# blackfin_e_lcd_keypad.net
KiCad netlist of a schematic drawn in Altium Designer
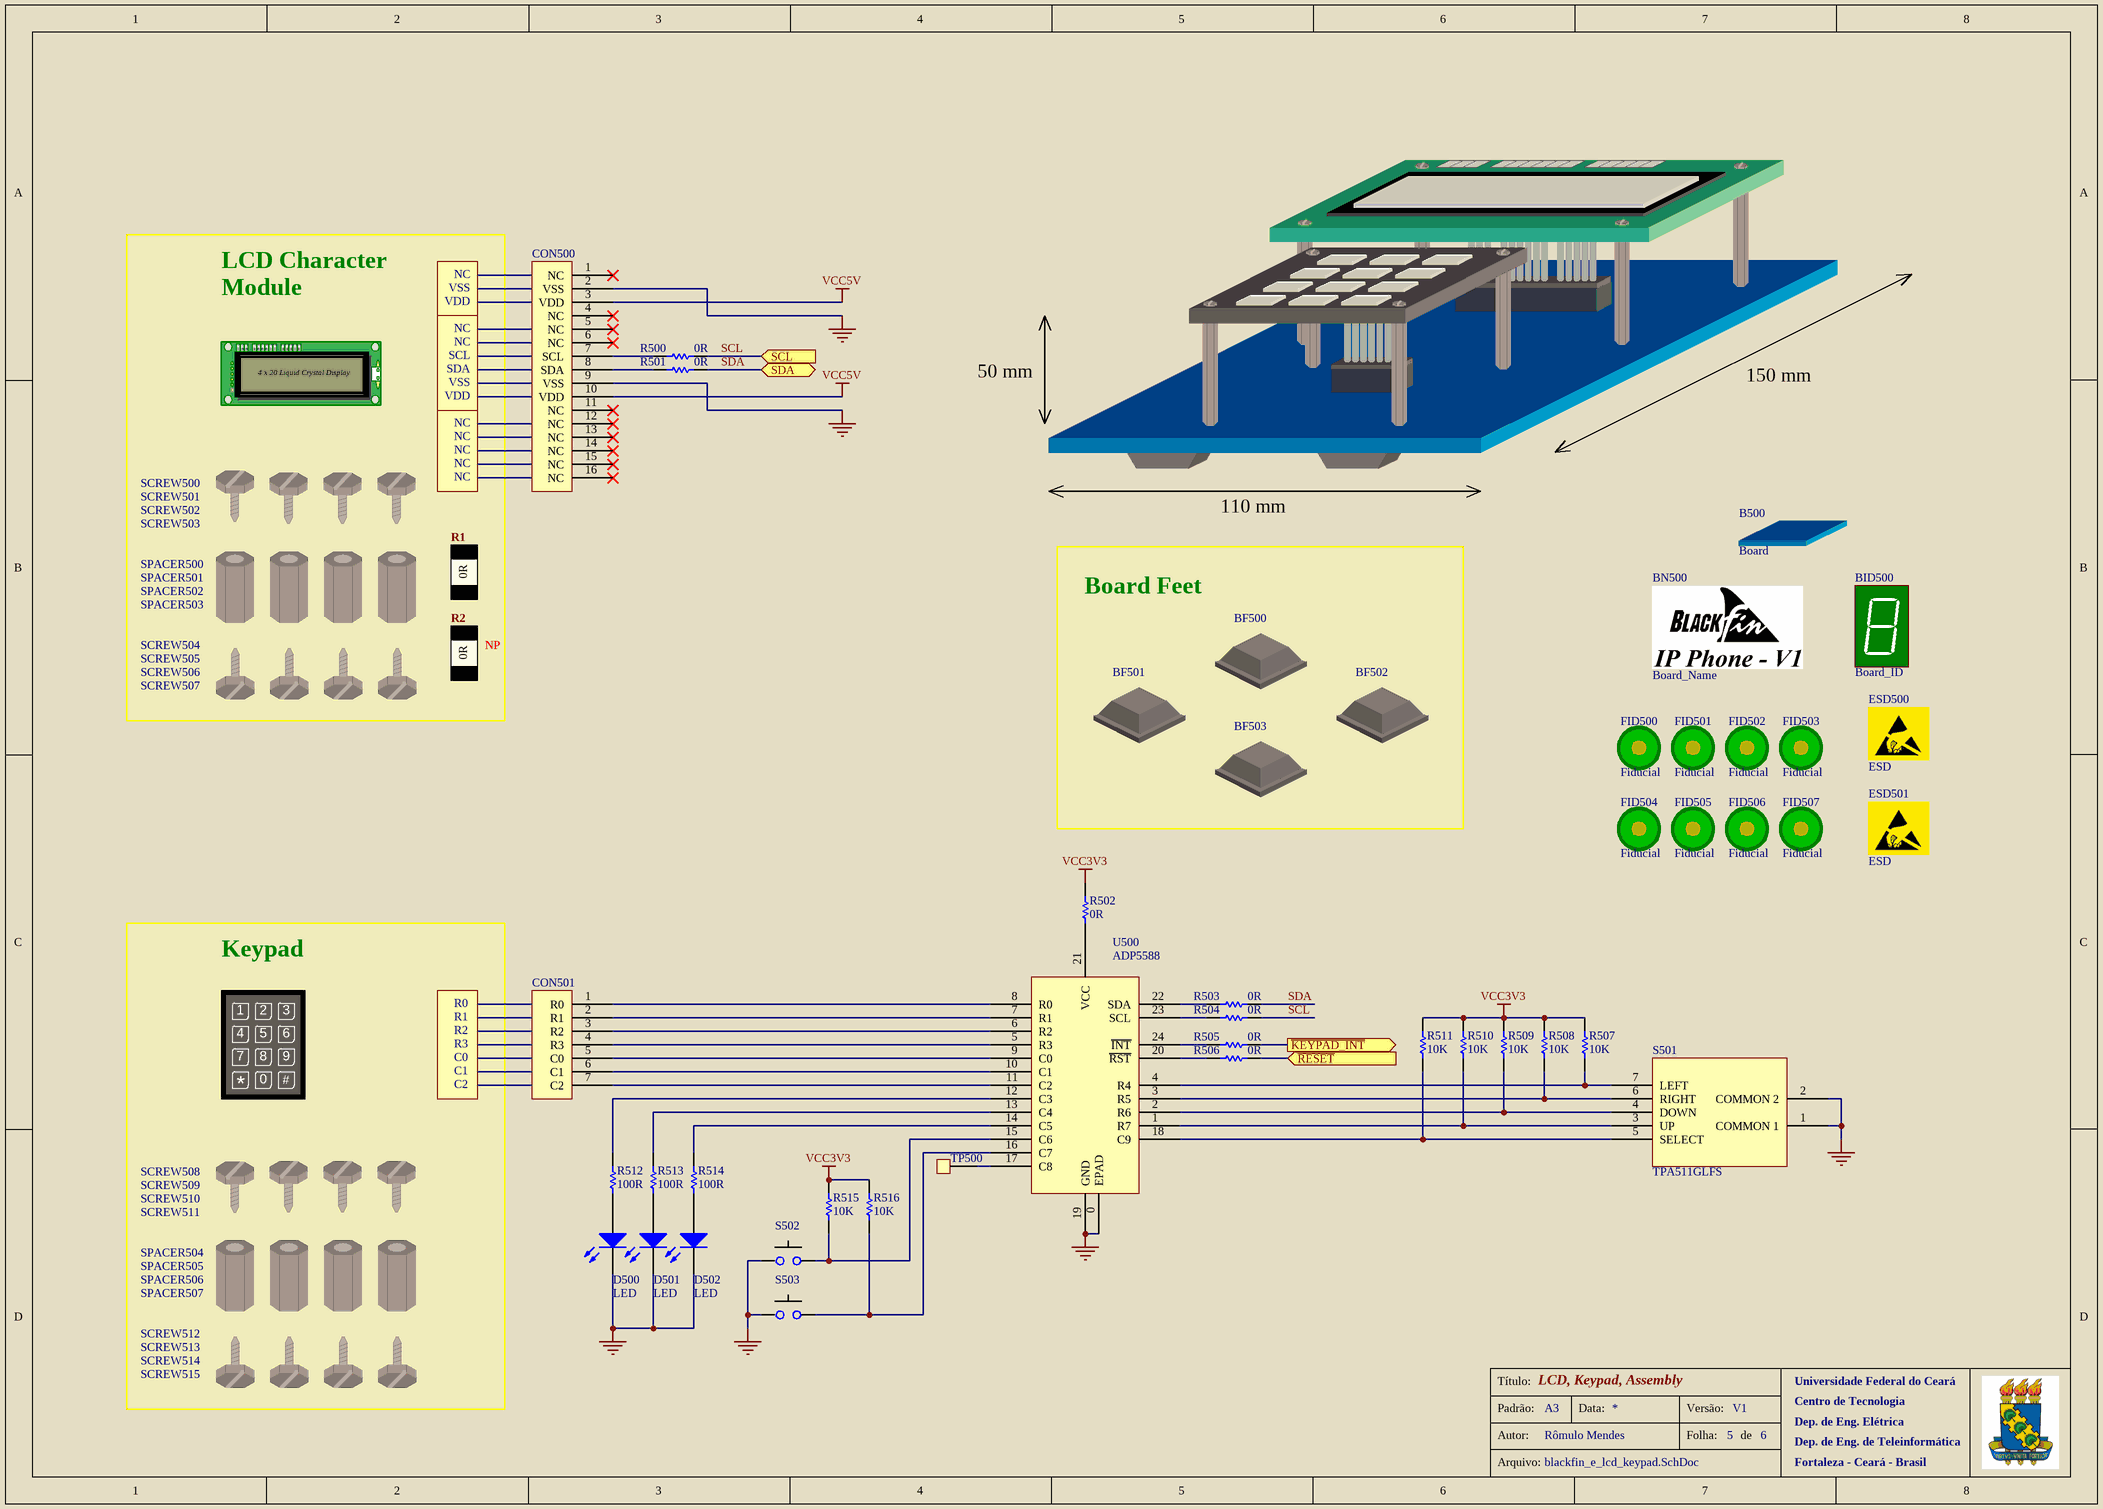
[diagram p0: blackfin_e_lcd_keypad.SchDoc]

(export (version "E")
  (design (tool "Eeschema 10.0.6"))
  (components
    (comp (ref "B500")
      (value "Board")
      (fields (field (name "EVENDORPART#") "NÃO SE APLICA"))
      (libsource (lib "blackfin_schlib") (part "Board"))
    )
    (comp (ref "BF500")
      (value "Board Foot")
      (footprint "blackfin_pcblib:Board Foot (Hemisphere)")
      (fields
        (field (name "EVENDORPART#") "517-SJ-5003BK")
        (field (name "PART#") "SJ-5003 (BLACK)")
        (field (name "MANUFACTURER") "3M Electronic Specialty")
      )
      (libsource (lib "*") (part "Board Foot"))
    )
    (comp (ref "BF501")
      (value "Board Foot")
      (footprint "blackfin_pcblib:Board Foot (Hemisphere)")
      (fields
        (field (name "EVENDORPART#") "517-SJ-5003BK")
        (field (name "PART#") "SJ-5003 (BLACK)")
        (field (name "MANUFACTURER") "3M Electronic Specialty")
      )
      (libsource (lib "*") (part "Board Foot"))
    )
    (comp (ref "BF502")
      (value "Board Foot")
      (footprint "blackfin_pcblib:Board Foot (Hemisphere)")
      (fields
        (field (name "EVENDORPART#") "517-SJ-5003BK")
        (field (name "PART#") "SJ-5003 (BLACK)")
        (field (name "MANUFACTURER") "3M Electronic Specialty")
      )
      (libsource (lib "*") (part "Board Foot"))
    )
    (comp (ref "BF503")
      (value "Board Foot")
      (footprint "blackfin_pcblib:Board Foot (Hemisphere)")
      (fields
        (field (name "EVENDORPART#") "517-SJ-5003BK")
        (field (name "PART#") "SJ-5003 (BLACK)")
        (field (name "MANUFACTURER") "3M Electronic Specialty")
      )
      (libsource (lib "*") (part "Board Foot"))
    )
    (comp (ref "BID500")
      (value "Board_ID")
      (footprint "blackfin_pcblib:BOARD_ID")
      (fields (field (name "EVENDORPART#") "NÃO SE APLICA"))
      (libsource (lib "blackfin_schlib") (part "Board_ID"))
    )
    (comp (ref "BN500")
      (value "Board_Name")
      (footprint "blackfin_pcblib:LOGO")
      (fields (field (name "EVENDORPART#") "NÃO SE APLICA"))
      (libsource (lib "blackfin_schlib") (part "Board_Name"))
    )
    (comp (ref "CON500")
      (value "LCD_Connector")
      (footprint "blackfin_pcblib:SOCKET_1x16")
      (fields (field (name "EVENDORPART#") "SSM-116-L-SV") (field (name "MANUFACTURER") "Samtec"))
      (libsource (lib "blackfin_schlib") (part "LCD_Connector"))
    )
    (comp (ref "CON501")
      (value "Keypad_Connector")
      (footprint "blackfin_pcblib:SOCKET_1x7")
      (fields (field (name "EVENDORPART#") "SSM-107-L-SV") (field (name "MANUFACTURER") "Samtec"))
      (libsource (lib "blackfin_schlib") (part "Keypad_Connector"))
    )
    (comp (ref "D500")
      (value "LED")
      (footprint "blackfin_pcblib:LED_0603")
      (description "Red LED")
      (fields (field (name "EVENDORPART#") "638-QTLP600C2TR") (field (name "MANUFACTURER") "Everlight"))
      (libsource (lib "blackfin_schlib") (part "LED"))
    )
    (comp (ref "D501")
      (value "LED")
      (footprint "blackfin_pcblib:LED_0603")
      (description "Red LED")
      (fields (field (name "EVENDORPART#") "638-QTLP600C2TR") (field (name "MANUFACTURER") "Everlight"))
      (libsource (lib "blackfin_schlib") (part "LED"))
    )
    (comp (ref "D502")
      (value "LED")
      (footprint "blackfin_pcblib:LED_0603")
      (description "Red LED")
      (fields (field (name "EVENDORPART#") "638-QTLP600C2TR") (field (name "MANUFACTURER") "Everlight"))
      (libsource (lib "blackfin_schlib") (part "LED"))
    )
    (comp (ref "ESD500")
      (value "ESD")
      (footprint "blackfin_pcblib:ESD")
      (fields (field (name "EVENDORPART#") "NÃO SE APLICA"))
      (libsource (lib "blackfin_schlib") (part "ESD"))
    )
    (comp (ref "ESD501")
      (value "ESD")
      (footprint "blackfin_pcblib:ESD")
      (fields (field (name "EVENDORPART#") "NÃO SE APLICA"))
      (libsource (lib "blackfin_schlib") (part "ESD"))
    )
    (comp (ref "FID500")
      (value "Fiducial")
      (footprint "blackfin_pcblib:Fiducial")
      (fields (field (name "EVENDORPART#") "NÃO SE APLICA"))
      (libsource (lib "blackfin_schlib") (part "Fiducial"))
    )
    (comp (ref "FID501")
      (value "Fiducial")
      (footprint "blackfin_pcblib:Fiducial")
      (fields (field (name "EVENDORPART#") "NÃO SE APLICA"))
      (libsource (lib "blackfin_schlib") (part "Fiducial"))
    )
    (comp (ref "FID502")
      (value "Fiducial")
      (footprint "blackfin_pcblib:Fiducial")
      (fields (field (name "EVENDORPART#") "NÃO SE APLICA"))
      (libsource (lib "blackfin_schlib") (part "Fiducial"))
    )
    (comp (ref "FID503")
      (value "Fiducial")
      (footprint "blackfin_pcblib:Fiducial")
      (fields (field (name "EVENDORPART#") "NÃO SE APLICA"))
      (libsource (lib "blackfin_schlib") (part "Fiducial"))
    )
    (comp (ref "FID504")
      (value "Fiducial")
      (footprint "blackfin_pcblib:Fiducial")
      (fields (field (name "EVENDORPART#") "NÃO SE APLICA"))
      (libsource (lib "blackfin_schlib") (part "Fiducial"))
    )
    (comp (ref "FID505")
      (value "Fiducial")
      (footprint "blackfin_pcblib:Fiducial")
      (fields (field (name "EVENDORPART#") "NÃO SE APLICA"))
      (libsource (lib "blackfin_schlib") (part "Fiducial"))
    )
    (comp (ref "FID506")
      (value "Fiducial")
      (footprint "blackfin_pcblib:Fiducial")
      (fields (field (name "EVENDORPART#") "NÃO SE APLICA"))
      (libsource (lib "blackfin_schlib") (part "Fiducial"))
    )
    (comp (ref "FID507")
      (value "Fiducial")
      (footprint "blackfin_pcblib:Fiducial")
      (fields (field (name "EVENDORPART#") "NÃO SE APLICA"))
      (libsource (lib "blackfin_schlib") (part "Fiducial"))
    )
    (comp (ref "KEYPAD_HEADER500")
      (value "Keypad_Header_1x7")
      (fields (field (name "EVENDORPART#") "ESQ-107-34-L-S") (field (name "MANUFACTURER") "Samtec"))
      (libsource (lib "blackfin_schlib") (part "Keypad_Header_1x7"))
    )
    (comp (ref "LCD500")
      (value "LCD")
      (footprint "blackfin_pcblib:LCD")
      (fields
        (field (name "EVENDORPART#") "763-0420D3Z-FL-GBW")
        (field (name "PART#") "NHD-0420D3Z-FL-GBW")
        (field (name "MANUFACTURER") "Newhaven")
      )
      (libsource (lib "*") (part "LCD"))
    )
    (comp (ref "LCD_HEADER500")
      (value "LCD_Header_1x3")
      (fields (field (name "EVENDORPART#") "DW-03-12-F-S-694") (field (name "MANUFACTURER") "Samtec"))
      (libsource (lib "blackfin_schlib") (part "LCD_Header_1x3"))
    )
    (comp (ref "LCD_HEADER501")
      (value "LCD_Header_1x6")
      (fields (field (name "EVENDORPART#") "DW-06-12-F-S-694") (field (name "MANUFACTURER") "Samtec"))
      (libsource (lib "blackfin_schlib") (part "LCD_Header_1x6"))
    )
    (comp (ref "LCD_HEADER502")
      (value "LCD_Header_1x5")
      (fields (field (name "EVENDORPART#") "DW-05-12-F-S-694") (field (name "MANUFACTURER") "Samtec"))
      (libsource (lib "blackfin_schlib") (part "LCD_Header_1x5"))
    )
    (comp (ref "LCD_RES500")
      (value "LCD_Resistor")
      (fields
        (field (name "EVENDORPART#") "71-CRCW0805-0-E3")
        (field (name "MANUFACTURER") "Vishay/Dale")
        (field (name "PART#") "CRCW08050000Z0EA")
      )
      (libsource (lib "blackfin_schlib") (part "LCD_Resistor"))
    )
    (comp (ref "LCD_RES501")
      (value "LCD_Resistor")
      (fields
        (field (name "EVENDORPART#") "71-CRCW0805-0-E3")
        (field (name "MANUFACTURER") "Vishay/Dale")
        (field (name "PART#") "CRCW08050000Z0EA")
      )
      (libsource (lib "blackfin_schlib") (part "LCD_Resistor"))
    )
    (comp (ref "R500")
      (value "0R")
      (footprint "blackfin_pcblib:R_0603")
      (fields
        (field (name "EVENDORPART#") "71-CRCW06030000Z0EB")
        (field (name "PART#") "CRCW06030000Z0EB")
        (field (name "MANUFACTURER") "Vishay/Dale")
      )
      (libsource (lib "blackfin_schlib") (part "Resistor"))
    )
    (comp (ref "R501")
      (value "0R")
      (footprint "blackfin_pcblib:R_0603")
      (fields
        (field (name "EVENDORPART#") "71-CRCW06030000Z0EB")
        (field (name "PART#") "CRCW06030000Z0EB")
        (field (name "MANUFACTURER") "Vishay/Dale")
      )
      (libsource (lib "blackfin_schlib") (part "Resistor"))
    )
    (comp (ref "R502")
      (value "0R")
      (footprint "blackfin_pcblib:R_0603")
      (fields
        (field (name "EVENDORPART#") "71-CRCW06030000Z0EB")
        (field (name "PART#") "CRCW06030000Z0EB")
        (field (name "MANUFACTURER") "Vishay/Dale")
      )
      (libsource (lib "blackfin_schlib") (part "Resistor"))
    )
    (comp (ref "R503")
      (value "0R")
      (footprint "blackfin_pcblib:R_0603")
      (fields
        (field (name "EVENDORPART#") "71-CRCW06030000Z0EB")
        (field (name "PART#") "CRCW06030000Z0EB")
        (field (name "MANUFACTURER") "Vishay/Dale")
      )
      (libsource (lib "blackfin_schlib") (part "Resistor"))
    )
    (comp (ref "R504")
      (value "0R")
      (footprint "blackfin_pcblib:R_0603")
      (fields
        (field (name "EVENDORPART#") "71-CRCW06030000Z0EB")
        (field (name "PART#") "CRCW06030000Z0EB")
        (field (name "MANUFACTURER") "Vishay/Dale")
      )
      (libsource (lib "blackfin_schlib") (part "Resistor"))
    )
    (comp (ref "R505")
      (value "0R")
      (footprint "blackfin_pcblib:R_0603")
      (fields
        (field (name "EVENDORPART#") "71-CRCW06030000Z0EB")
        (field (name "PART#") "CRCW06030000Z0EB")
        (field (name "MANUFACTURER") "Vishay/Dale")
      )
      (libsource (lib "blackfin_schlib") (part "Resistor"))
    )
    (comp (ref "R506")
      (value "0R")
      (footprint "blackfin_pcblib:R_0603")
      (fields
        (field (name "EVENDORPART#") "71-CRCW06030000Z0EB")
        (field (name "PART#") "CRCW06030000Z0EB")
        (field (name "MANUFACTURER") "Vishay/Dale")
      )
      (libsource (lib "blackfin_schlib") (part "Resistor"))
    )
    (comp (ref "R507")
      (value "10K")
      (footprint "blackfin_pcblib:R_0603")
      (fields
        (field (name "EVENDORPART#") "71-CRCW0603-10K-E3")
        (field (name "PART#") "CRCW060310K0FKEA")
        (field (name "MANUFACTURER") "Vishay/Dale")
      )
      (libsource (lib "blackfin_schlib") (part "Resistor"))
    )
    (comp (ref "R508")
      (value "10K")
      (footprint "blackfin_pcblib:R_0603")
      (fields
        (field (name "EVENDORPART#") "71-CRCW0603-10K-E3")
        (field (name "PART#") "CRCW060310K0FKEA")
        (field (name "MANUFACTURER") "Vishay/Dale")
      )
      (libsource (lib "blackfin_schlib") (part "Resistor"))
    )
    (comp (ref "R509")
      (value "10K")
      (footprint "blackfin_pcblib:R_0603")
      (fields
        (field (name "EVENDORPART#") "71-CRCW0603-10K-E3")
        (field (name "PART#") "CRCW060310K0FKEA")
        (field (name "MANUFACTURER") "Vishay/Dale")
      )
      (libsource (lib "blackfin_schlib") (part "Resistor"))
    )
    (comp (ref "R510")
      (value "10K")
      (footprint "blackfin_pcblib:R_0603")
      (fields
        (field (name "EVENDORPART#") "71-CRCW0603-10K-E3")
        (field (name "PART#") "CRCW060310K0FKEA")
        (field (name "MANUFACTURER") "Vishay/Dale")
      )
      (libsource (lib "blackfin_schlib") (part "Resistor"))
    )
    (comp (ref "R511")
      (value "10K")
      (footprint "blackfin_pcblib:R_0603")
      (fields
        (field (name "EVENDORPART#") "71-CRCW0603-10K-E3")
        (field (name "PART#") "CRCW060310K0FKEA")
        (field (name "MANUFACTURER") "Vishay/Dale")
      )
      (libsource (lib "blackfin_schlib") (part "Resistor"))
    )
    (comp (ref "R512")
      (value "100R")
      (footprint "blackfin_pcblib:R_0603")
      (fields
        (field (name "EVENDORPART#") "71-CRCW0603-100-E3")
        (field (name "PART#") "CRCW0603100RFKEA")
        (field (name "MANUFACTURER") "Vishay/Dale")
      )
      (libsource (lib "blackfin_schlib") (part "Resistor"))
    )
    (comp (ref "R513")
      (value "100R")
      (footprint "blackfin_pcblib:R_0603")
      (fields
        (field (name "EVENDORPART#") "71-CRCW0603-100-E3")
        (field (name "PART#") "CRCW0603100RFKEA")
        (field (name "MANUFACTURER") "Vishay/Dale")
      )
      (libsource (lib "blackfin_schlib") (part "Resistor"))
    )
    (comp (ref "R514")
      (value "100R")
      (footprint "blackfin_pcblib:R_0603")
      (fields
        (field (name "EVENDORPART#") "71-CRCW0603-100-E3")
        (field (name "PART#") "CRCW0603100RFKEA")
        (field (name "MANUFACTURER") "Vishay/Dale")
      )
      (libsource (lib "blackfin_schlib") (part "Resistor"))
    )
    (comp (ref "R515")
      (value "10K")
      (footprint "blackfin_pcblib:R_0603")
      (fields
        (field (name "EVENDORPART#") "71-CRCW0603-10K-E3")
        (field (name "PART#") "CRCW060310K0FKEA")
        (field (name "MANUFACTURER") "Vishay/Dale")
      )
      (libsource (lib "blackfin_schlib") (part "Resistor"))
    )
    (comp (ref "R516")
      (value "10K")
      (footprint "blackfin_pcblib:R_0603")
      (fields
        (field (name "EVENDORPART#") "71-CRCW0603-10K-E3")
        (field (name "PART#") "CRCW060310K0FKEA")
        (field (name "MANUFACTURER") "Vishay/Dale")
      )
      (libsource (lib "blackfin_schlib") (part "Resistor"))
    )
    (comp (ref "S500")
      (value "Keypad")
      (footprint "blackfin_pcblib:Keypad")
      (fields
        (field (name "EVENDORPART#") "GH5009-ND")
        (field (name "PART#") "96AB2-152-R")
        (field (name "MANUFACTURER") "Grayhill Inc")
      )
      (libsource (lib "blackfin_schlib") (part "Keypad"))
    )
    (comp (ref "S501")
      (value "TPA511GLFS")
      (footprint "blackfin_pcblib:TPA511GLFS")
      (fields (field (name "EVENDORPART#") "611-TPA511GLFS") (field (name "MANUFACTURER") "C&K Components"))
      (libsource (lib "blackfin_schlib") (part "TPA511GLFS"))
    )
    (comp (ref "S502")
      (value "Push Button")
      (footprint "blackfin_pcblib:Push Button")
      (fields
        (field (name "EVENDORPART#") "611-PTS645SH50SMTRLF")
        (field (name "PART#") "PTS645SH50SMTRLFS")
        (field (name "MANUFACTURER") "C&K Components")
      )
      (libsource (lib "*") (part "Push Button"))
    )
    (comp (ref "S503")
      (value "Push Button")
      (footprint "blackfin_pcblib:Push Button")
      (fields
        (field (name "EVENDORPART#") "611-PTS645SH50SMTRLF")
        (field (name "PART#") "PTS645SH50SMTRLFS")
        (field (name "MANUFACTURER") "C&K Components")
      )
      (libsource (lib "*") (part "Push Button"))
    )
    (comp (ref "SCREW500")
      (value "Screw")
      (fields
        (field (name "EVENDORPART#") "534-29301")
        (field (name "PART#") "29301")
        (field (name "MANUFACTURER") "Keystone Electronics")
      )
      (libsource (lib "*") (part "Screw"))
    )
    (comp (ref "SCREW501")
      (value "Screw")
      (fields
        (field (name "EVENDORPART#") "534-29301")
        (field (name "PART#") "29301")
        (field (name "MANUFACTURER") "Keystone Electronics")
      )
      (libsource (lib "*") (part "Screw"))
    )
    (comp (ref "SCREW502")
      (value "Screw")
      (fields
        (field (name "EVENDORPART#") "534-29301")
        (field (name "PART#") "29301")
        (field (name "MANUFACTURER") "Keystone Electronics")
      )
      (libsource (lib "*") (part "Screw"))
    )
    (comp (ref "SCREW503")
      (value "Screw")
      (fields
        (field (name "EVENDORPART#") "534-29301")
        (field (name "PART#") "29301")
        (field (name "MANUFACTURER") "Keystone Electronics")
      )
      (libsource (lib "*") (part "Screw"))
    )
    (comp (ref "SCREW504")
      (value "Screw")
      (fields
        (field (name "EVENDORPART#") "534-29301")
        (field (name "PART#") "29301")
        (field (name "MANUFACTURER") "Keystone Electronics")
      )
      (libsource (lib "*") (part "Screw"))
    )
    (comp (ref "SCREW505")
      (value "Screw")
      (fields
        (field (name "EVENDORPART#") "534-29301")
        (field (name "PART#") "29301")
        (field (name "MANUFACTURER") "Keystone Electronics")
      )
      (libsource (lib "*") (part "Screw"))
    )
    (comp (ref "SCREW506")
      (value "Screw")
      (fields
        (field (name "EVENDORPART#") "534-29301")
        (field (name "PART#") "29301")
        (field (name "MANUFACTURER") "Keystone Electronics")
      )
      (libsource (lib "*") (part "Screw"))
    )
    (comp (ref "SCREW507")
      (value "Screw")
      (fields
        (field (name "EVENDORPART#") "534-29301")
        (field (name "PART#") "29301")
        (field (name "MANUFACTURER") "Keystone Electronics")
      )
      (libsource (lib "*") (part "Screw"))
    )
    (comp (ref "SCREW508")
      (value "Screw")
      (fields
        (field (name "EVENDORPART#") "534-29301")
        (field (name "PART#") "29301")
        (field (name "MANUFACTURER") "Keystone Electronics")
      )
      (libsource (lib "*") (part "Screw"))
    )
    (comp (ref "SCREW509")
      (value "Screw")
      (fields
        (field (name "EVENDORPART#") "534-29301")
        (field (name "PART#") "29301")
        (field (name "MANUFACTURER") "Keystone Electronics")
      )
      (libsource (lib "*") (part "Screw"))
    )
    (comp (ref "SCREW510")
      (value "Screw")
      (fields
        (field (name "EVENDORPART#") "534-29301")
        (field (name "PART#") "29301")
        (field (name "MANUFACTURER") "Keystone Electronics")
      )
      (libsource (lib "*") (part "Screw"))
    )
    (comp (ref "SCREW511")
      (value "Screw")
      (fields
        (field (name "EVENDORPART#") "534-29301")
        (field (name "PART#") "29301")
        (field (name "MANUFACTURER") "Keystone Electronics")
      )
      (libsource (lib "*") (part "Screw"))
    )
    (comp (ref "SCREW512")
      (value "Screw")
      (fields
        (field (name "EVENDORPART#") "534-29301")
        (field (name "PART#") "29301")
        (field (name "MANUFACTURER") "Keystone Electronics")
      )
      (libsource (lib "*") (part "Screw"))
    )
    (comp (ref "SCREW513")
      (value "Screw")
      (fields
        (field (name "EVENDORPART#") "534-29301")
        (field (name "PART#") "29301")
        (field (name "MANUFACTURER") "Keystone Electronics")
      )
      (libsource (lib "*") (part "Screw"))
    )
    (comp (ref "SCREW514")
      (value "Screw")
      (fields
        (field (name "EVENDORPART#") "534-29301")
        (field (name "PART#") "29301")
        (field (name "MANUFACTURER") "Keystone Electronics")
      )
      (libsource (lib "*") (part "Screw"))
    )
    (comp (ref "SCREW515")
      (value "Screw")
      (fields
        (field (name "EVENDORPART#") "534-29301")
        (field (name "PART#") "29301")
        (field (name "MANUFACTURER") "Keystone Electronics")
      )
      (libsource (lib "*") (part "Screw"))
    )
    (comp (ref "SPACER500")
      (value "Spacer")
      (fields
        (field (name "EVENDORPART#") "534-24428")
        (field (name "MANUFACTURER") "Keystone Electronics")
        (field (name "PART#") "24428")
      )
      (libsource (lib "blackfin_schlib") (part "Spacer"))
    )
    (comp (ref "SPACER501")
      (value "Spacer")
      (fields
        (field (name "EVENDORPART#") "534-24428")
        (field (name "MANUFACTURER") "Keystone Electronics")
        (field (name "PART#") "24428")
      )
      (libsource (lib "blackfin_schlib") (part "Spacer"))
    )
    (comp (ref "SPACER502")
      (value "Spacer")
      (fields
        (field (name "EVENDORPART#") "534-24428")
        (field (name "MANUFACTURER") "Keystone Electronics")
        (field (name "PART#") "24428")
      )
      (libsource (lib "blackfin_schlib") (part "Spacer"))
    )
    (comp (ref "SPACER503")
      (value "Spacer")
      (fields
        (field (name "EVENDORPART#") "534-24428")
        (field (name "MANUFACTURER") "Keystone Electronics")
        (field (name "PART#") "24428")
      )
      (libsource (lib "blackfin_schlib") (part "Spacer"))
    )
    (comp (ref "SPACER504")
      (value "Spacer")
      (fields
        (field (name "EVENDORPART#") "534-24428")
        (field (name "MANUFACTURER") "Keystone Electronics")
        (field (name "PART#") "24428")
      )
      (libsource (lib "blackfin_schlib") (part "Spacer"))
    )
    (comp (ref "SPACER505")
      (value "Spacer")
      (fields
        (field (name "EVENDORPART#") "534-24428")
        (field (name "MANUFACTURER") "Keystone Electronics")
        (field (name "PART#") "24428")
      )
      (libsource (lib "blackfin_schlib") (part "Spacer"))
    )
    (comp (ref "SPACER506")
      (value "Spacer")
      (fields
        (field (name "EVENDORPART#") "534-24428")
        (field (name "MANUFACTURER") "Keystone Electronics")
        (field (name "PART#") "24428")
      )
      (libsource (lib "blackfin_schlib") (part "Spacer"))
    )
    (comp (ref "SPACER507")
      (value "Spacer")
      (fields
        (field (name "EVENDORPART#") "534-24428")
        (field (name "MANUFACTURER") "Keystone Electronics")
        (field (name "PART#") "24428")
      )
      (libsource (lib "blackfin_schlib") (part "Spacer"))
    )
    (comp (ref "TP500")
      (value "Test Point")
      (footprint "blackfin_pcblib:Test Point")
      (fields (field (name "EVENDORPART#") "NÃO SE APLICA"))
      (libsource (lib "blackfin_schlib") (part "Test Point"))
    )
    (comp (ref "U500")
      (value "ADP5588")
      (footprint "blackfin_pcblib:QFN-24")
      (fields
        (field (name "EVENDORPART#") "ADP5588ACPZ-R7CT-ND")
        (field (name "PART#") "ADP5588ACPZ-R7")
        (field (name "MANUFACTURER") "Analog Devices")
      )
      (libsource (lib "blackfin_schlib") (part "ADP5588"))
    )
  )
  (nets
    (net (code "1") (name "/SCL") (class "Default")
      (node (ref "R500") (pin "2") (pinfunction "2_2") (pintype "passive"))
      (node (ref "R504") (pin "2") (pinfunction "2_2") (pintype "passive"))
    )
    (net (code "2") (name "/SDA") (class "Default")
      (node (ref "R501") (pin "2") (pinfunction "2_2") (pintype "passive"))
      (node (ref "R503") (pin "2") (pinfunction "2_2") (pintype "passive"))
    )
    (net (code "3") (name "/~{KEYPAD_INT}") (class "Default")
      (node (ref "R505") (pin "2") (pinfunction "2_2") (pintype "passive"))
    )
    (net (code "4") (name "/~{RESET}") (class "Default")
      (node (ref "R506") (pin "2") (pinfunction "2_2") (pintype "passive"))
    )
    (net (code "5") (name "GND") (class "Default")
      (node (ref "CON500") (pin "2") (pinfunction "VSS_2") (pintype "passive"))
      (node (ref "CON500") (pin "9") (pinfunction "VSS_9") (pintype "passive"))
      (node (ref "D500") (pin "2") (pinfunction "K_2") (pintype "passive"))
      (node (ref "D501") (pin "2") (pinfunction "K_2") (pintype "passive"))
      (node (ref "D502") (pin "2") (pinfunction "K_2") (pintype "passive"))
      (node (ref "S501") (pin "1") (pinfunction "COMMON_1_1") (pintype "passive"))
      (node (ref "S501") (pin "2") (pinfunction "COMMON_2_2") (pintype "passive"))
      (node (ref "S502") (pin "1") (pinfunction "1_1") (pintype "passive"))
      (node (ref "S503") (pin "1") (pinfunction "1_1") (pintype "passive"))
      (node (ref "U500") (pin "0") (pinfunction "EPAD_0") (pintype "passive"))
      (node (ref "U500") (pin "19") (pinfunction "GND_19") (pintype "passive"))
    )
    (net (code "6") (name "Net-(CON500-SCL)") (class "Default")
      (node (ref "CON500") (pin "7") (pinfunction "SCL_7") (pintype "passive"))
      (node (ref "R500") (pin "1") (pinfunction "1_1") (pintype "passive"))
    )
    (net (code "7") (name "Net-(CON500-SDA)") (class "Default")
      (node (ref "CON500") (pin "8") (pinfunction "SDA_8") (pintype "passive"))
      (node (ref "R501") (pin "1") (pinfunction "1_1") (pintype "passive"))
    )
    (net (code "8") (name "Net-(CON501-C0)") (class "Default")
      (node (ref "CON501") (pin "5") (pinfunction "C0_5") (pintype "passive"))
      (node (ref "U500") (pin "9") (pinfunction "C0_9") (pintype "passive"))
    )
    (net (code "9") (name "Net-(CON501-C1)") (class "Default")
      (node (ref "CON501") (pin "6") (pinfunction "C1_6") (pintype "passive"))
      (node (ref "U500") (pin "10") (pinfunction "C1_10") (pintype "passive"))
    )
    (net (code "10") (name "Net-(CON501-C2)") (class "Default")
      (node (ref "CON501") (pin "7") (pinfunction "C2_7") (pintype "passive"))
      (node (ref "U500") (pin "11") (pinfunction "C2_11") (pintype "passive"))
    )
    (net (code "11") (name "Net-(CON501-R0)") (class "Default")
      (node (ref "CON501") (pin "1") (pinfunction "R0_1") (pintype "passive"))
      (node (ref "U500") (pin "8") (pinfunction "R0_8") (pintype "passive"))
    )
    (net (code "12") (name "Net-(CON501-R1)") (class "Default")
      (node (ref "CON501") (pin "2") (pinfunction "R1_2") (pintype "passive"))
      (node (ref "U500") (pin "7") (pinfunction "R1_7") (pintype "passive"))
    )
    (net (code "13") (name "Net-(CON501-R2)") (class "Default")
      (node (ref "CON501") (pin "3") (pinfunction "R2_3") (pintype "passive"))
      (node (ref "U500") (pin "6") (pinfunction "R2_6") (pintype "passive"))
    )
    (net (code "14") (name "Net-(CON501-R3)") (class "Default")
      (node (ref "CON501") (pin "4") (pinfunction "R3_4") (pintype "passive"))
      (node (ref "U500") (pin "5") (pinfunction "R3_5") (pintype "passive"))
    )
    (net (code "15") (name "Net-(D500-A)") (class "Default")
      (node (ref "D500") (pin "1") (pinfunction "A_1") (pintype "passive"))
      (node (ref "R512") (pin "1") (pinfunction "1_1") (pintype "passive"))
    )
    (net (code "16") (name "Net-(D501-A)") (class "Default")
      (node (ref "D501") (pin "1") (pinfunction "A_1") (pintype "passive"))
      (node (ref "R513") (pin "1") (pinfunction "1_1") (pintype "passive"))
    )
    (net (code "17") (name "Net-(D502-A)") (class "Default")
      (node (ref "D502") (pin "1") (pinfunction "A_1") (pintype "passive"))
      (node (ref "R514") (pin "1") (pinfunction "1_1") (pintype "passive"))
    )
    (net (code "18") (name "Net-(S501-DOWN)") (class "Default")
      (node (ref "R509") (pin "2") (pinfunction "2_2") (pintype "passive"))
      (node (ref "S501") (pin "4") (pinfunction "DOWN_4") (pintype "passive"))
      (node (ref "U500") (pin "2") (pinfunction "R6_2") (pintype "passive"))
    )
    (net (code "19") (name "Net-(S501-LEFT)") (class "Default")
      (node (ref "R507") (pin "2") (pinfunction "2_2") (pintype "passive"))
      (node (ref "S501") (pin "7") (pinfunction "LEFT_7") (pintype "passive"))
      (node (ref "U500") (pin "4") (pinfunction "R4_4") (pintype "passive"))
    )
    (net (code "20") (name "Net-(S501-RIGHT)") (class "Default")
      (node (ref "R508") (pin "2") (pinfunction "2_2") (pintype "passive"))
      (node (ref "S501") (pin "6") (pinfunction "RIGHT_6") (pintype "passive"))
      (node (ref "U500") (pin "3") (pinfunction "R5_3") (pintype "passive"))
    )
    (net (code "21") (name "Net-(S501-SELECT)") (class "Default")
      (node (ref "R511") (pin "2") (pinfunction "2_2") (pintype "passive"))
      (node (ref "S501") (pin "5") (pinfunction "SELECT_5") (pintype "passive"))
      (node (ref "U500") (pin "18") (pinfunction "C9_18") (pintype "passive"))
    )
    (net (code "22") (name "Net-(S501-UP)") (class "Default")
      (node (ref "R510") (pin "2") (pinfunction "2_2") (pintype "passive"))
      (node (ref "S501") (pin "3") (pinfunction "UP_3") (pintype "passive"))
      (node (ref "U500") (pin "1") (pinfunction "R7_1") (pintype "passive"))
    )
    (net (code "23") (name "Net-(U500-C3)") (class "Default")
      (node (ref "R512") (pin "2") (pinfunction "2_2") (pintype "passive"))
      (node (ref "U500") (pin "12") (pinfunction "C3_12") (pintype "passive"))
    )
    (net (code "24") (name "Net-(U500-C4)") (class "Default")
      (node (ref "R513") (pin "2") (pinfunction "2_2") (pintype "passive"))
      (node (ref "U500") (pin "13") (pinfunction "C4_13") (pintype "passive"))
    )
    (net (code "25") (name "Net-(U500-C5)") (class "Default")
      (node (ref "R514") (pin "2") (pinfunction "2_2") (pintype "passive"))
      (node (ref "U500") (pin "14") (pinfunction "C5_14") (pintype "passive"))
    )
    (net (code "26") (name "Net-(U500-C6)") (class "Default")
      (node (ref "R515") (pin "2") (pinfunction "2_2") (pintype "passive"))
      (node (ref "S502") (pin "2") (pinfunction "2_2") (pintype "passive"))
      (node (ref "U500") (pin "15") (pinfunction "C6_15") (pintype "passive"))
    )
    (net (code "27") (name "Net-(U500-C7)") (class "Default")
      (node (ref "R516") (pin "2") (pinfunction "2_2") (pintype "passive"))
      (node (ref "S503") (pin "2") (pinfunction "2_2") (pintype "passive"))
      (node (ref "U500") (pin "16") (pinfunction "C7_16") (pintype "passive"))
    )
    (net (code "28") (name "Net-(U500-C8)") (class "Default")
      (node (ref "TP500") (pin "1") (pinfunction "1_1") (pintype "passive"))
      (node (ref "U500") (pin "17") (pinfunction "C8_17") (pintype "passive"))
    )
    (net (code "29") (name "Net-(U500-SCL)") (class "Default")
      (node (ref "R504") (pin "1") (pinfunction "1_1") (pintype "passive"))
      (node (ref "U500") (pin "23") (pinfunction "SCL_23") (pintype "passive"))
    )
    (net (code "30") (name "Net-(U500-SDA)") (class "Default")
      (node (ref "R503") (pin "1") (pinfunction "1_1") (pintype "passive"))
      (node (ref "U500") (pin "22") (pinfunction "SDA_22") (pintype "passive"))
    )
    (net (code "31") (name "Net-(U500-VCC)") (class "Default")
      (node (ref "R502") (pin "1") (pinfunction "1_1") (pintype "passive"))
      (node (ref "U500") (pin "21") (pinfunction "VCC_21") (pintype "passive"))
    )
    (net (code "32") (name "Net-(U500-~{INT})") (class "Default")
      (node (ref "R505") (pin "1") (pinfunction "1_1") (pintype "passive"))
      (node (ref "U500") (pin "24") (pinfunction "~{INT}_24") (pintype "passive"))
    )
    (net (code "33") (name "Net-(U500-~{RST})") (class "Default")
      (node (ref "R506") (pin "1") (pinfunction "1_1") (pintype "passive"))
      (node (ref "U500") (pin "20") (pinfunction "~{RST}_20") (pintype "passive"))
    )
    (net (code "34") (name "VCC3V3") (class "Default")
      (node (ref "R502") (pin "2") (pinfunction "2_2") (pintype "passive"))
      (node (ref "R507") (pin "1") (pinfunction "1_1") (pintype "passive"))
      (node (ref "R508") (pin "1") (pinfunction "1_1") (pintype "passive"))
      (node (ref "R509") (pin "1") (pinfunction "1_1") (pintype "passive"))
      (node (ref "R510") (pin "1") (pinfunction "1_1") (pintype "passive"))
      (node (ref "R511") (pin "1") (pinfunction "1_1") (pintype "passive"))
      (node (ref "R515") (pin "1") (pinfunction "1_1") (pintype "passive"))
      (node (ref "R516") (pin "1") (pinfunction "1_1") (pintype "passive"))
    )
    (net (code "35") (name "VCC5V") (class "Default")
      (node (ref "CON500") (pin "10") (pinfunction "VDD_10") (pintype "passive"))
      (node (ref "CON500") (pin "3") (pinfunction "VDD_3") (pintype "passive"))
    )
    (net (code "36") (name "unconnected-(CON500-NC-Pad1)") (class "Default")
      (node (ref "CON500") (pin "1") (pinfunction "NC_1") (pintype "passive+no_connect"))
    )
    (net (code "37") (name "unconnected-(CON500-NC-Pad4)") (class "Default")
      (node (ref "CON500") (pin "4") (pinfunction "NC_4") (pintype "passive+no_connect"))
    )
    (net (code "38") (name "unconnected-(CON500-NC-Pad5)") (class "Default")
      (node (ref "CON500") (pin "5") (pinfunction "NC_5") (pintype "passive+no_connect"))
    )
    (net (code "39") (name "unconnected-(CON500-NC-Pad6)") (class "Default")
      (node (ref "CON500") (pin "6") (pinfunction "NC_6") (pintype "passive+no_connect"))
    )
    (net (code "40") (name "unconnected-(CON500-NC-Pad11)") (class "Default")
      (node (ref "CON500") (pin "11") (pinfunction "NC_11") (pintype "passive+no_connect"))
    )
    (net (code "41") (name "unconnected-(CON500-NC-Pad12)") (class "Default")
      (node (ref "CON500") (pin "12") (pinfunction "NC_12") (pintype "passive+no_connect"))
    )
    (net (code "42") (name "unconnected-(CON500-NC-Pad13)") (class "Default")
      (node (ref "CON500") (pin "13") (pinfunction "NC_13") (pintype "passive+no_connect"))
    )
    (net (code "43") (name "unconnected-(CON500-NC-Pad14)") (class "Default")
      (node (ref "CON500") (pin "14") (pinfunction "NC_14") (pintype "passive+no_connect"))
    )
    (net (code "44") (name "unconnected-(CON500-NC-Pad15)") (class "Default")
      (node (ref "CON500") (pin "15") (pinfunction "NC_15") (pintype "passive+no_connect"))
    )
    (net (code "45") (name "unconnected-(CON500-NC-Pad16)") (class "Default")
      (node (ref "CON500") (pin "16") (pinfunction "NC_16") (pintype "passive+no_connect"))
    )
  )
)
